# untitled.net
KiCad netlist of a schematic drawn in EAGLE
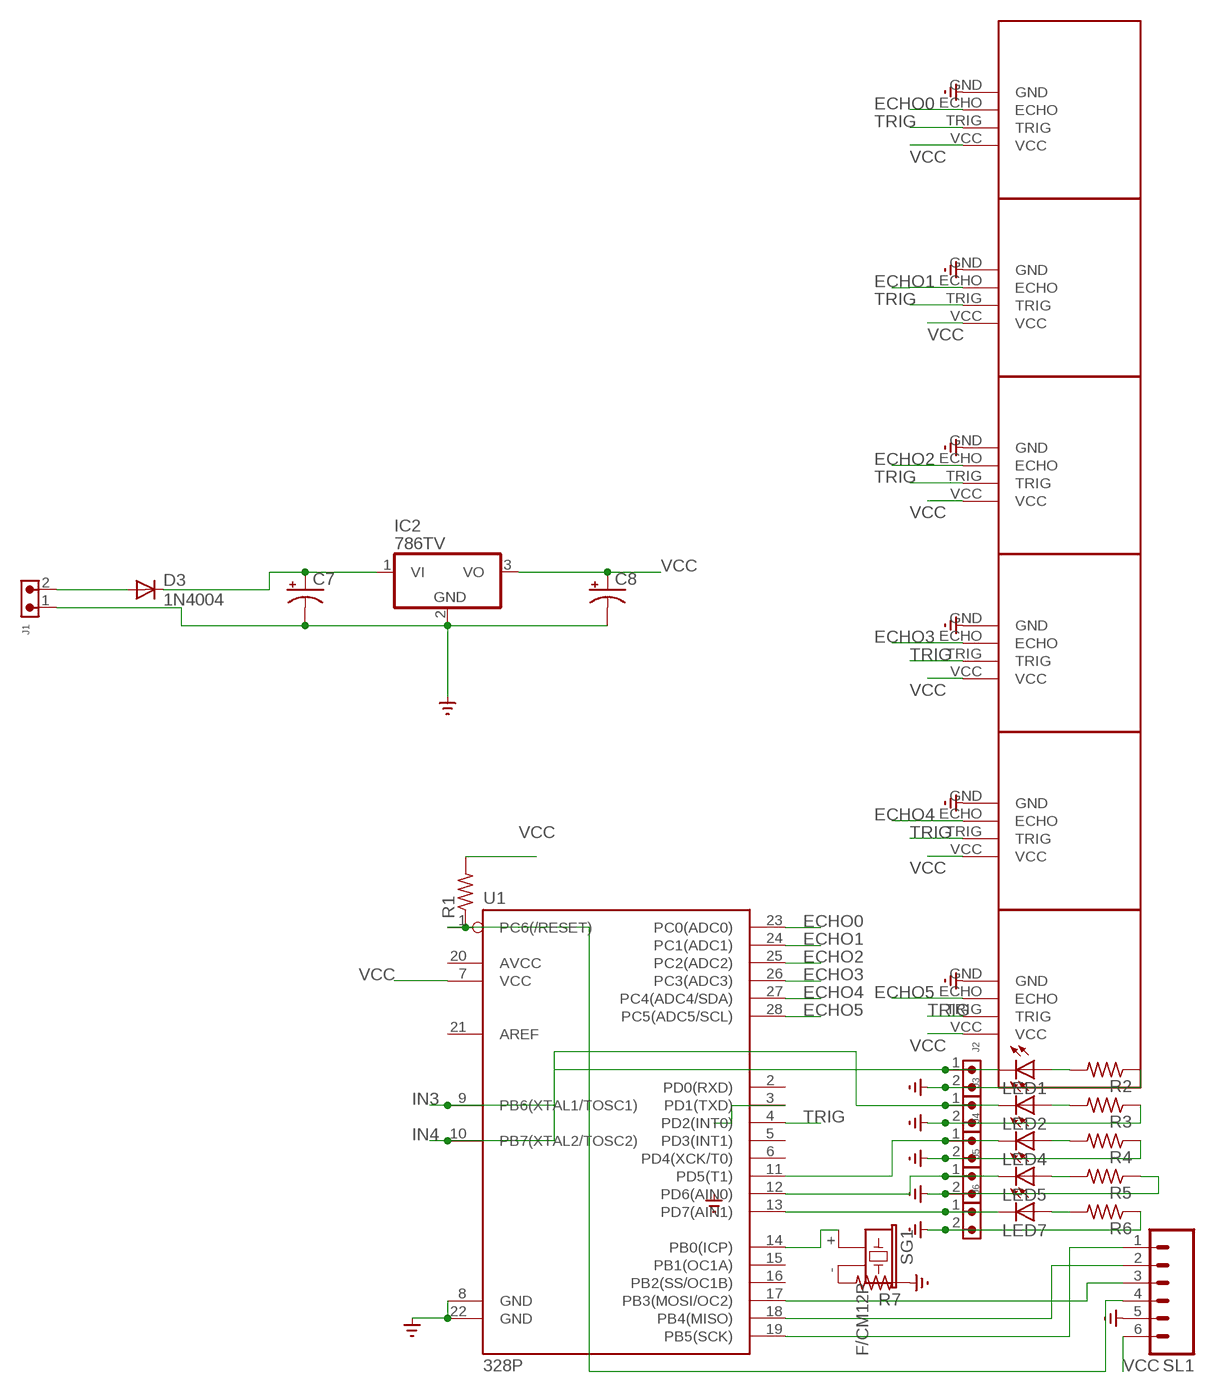
[diagram p0: schematic, sheet 1]

(export (version "E")
  (design (tool "Eeschema 10.0.6"))
  (components
    (comp (ref "C7")
      (value "CAPACITOR-PE5-10.5")
      (footprint "eagle-import:E5-10,5")
      (libsource (lib "eagle-import") (part "CAPACITOR-PE5-10.5"))
    )
    (comp (ref "C8")
      (value "CAPACITOR-PE5-6")
      (footprint "eagle-import:E5-6")
      (libsource (lib "eagle-import") (part "CAPACITOR-PE5-6"))
    )
    (comp (ref "D3")
      (value "1N4004")
      (footprint "eagle-import:DO41-10")
      (libsource (lib "eagle-import") (part "1N4004"))
    )
    (comp (ref "IC2")
      (value "786TV")
      (footprint "eagle-import:TO220V")
      (libsource (lib "eagle-import") (part "78TV6"))
    )
    (comp (ref "J1")
      (value "691305530002")
      (footprint "eagle-import:691305530002")
      (libsource (lib "eagle-import") (part "691305530002"))
    )
    (comp (ref "J2")
      (value "691305530002")
      (footprint "eagle-import:691305530002")
      (libsource (lib "eagle-import") (part "691305530002"))
    )
    (comp (ref "J3")
      (value "691305530002")
      (footprint "eagle-import:691305530002")
      (libsource (lib "eagle-import") (part "691305530002"))
    )
    (comp (ref "J4")
      (value "691305530002")
      (footprint "eagle-import:691305530002")
      (libsource (lib "eagle-import") (part "691305530002"))
    )
    (comp (ref "J5")
      (value "691305530002")
      (footprint "eagle-import:691305530002")
      (libsource (lib "eagle-import") (part "691305530002"))
    )
    (comp (ref "J6")
      (value "691305530002")
      (footprint "eagle-import:691305530002")
      (libsource (lib "eagle-import") (part "691305530002"))
    )
    (comp (ref "LED1")
      (value "LED5MM")
      (footprint "eagle-import:LED5MM")
      (libsource (lib "eagle-import") (part "LED5MM"))
    )
    (comp (ref "LED2")
      (value "LED5MM")
      (footprint "eagle-import:LED5MM")
      (libsource (lib "eagle-import") (part "LED5MM"))
    )
    (comp (ref "LED4")
      (value "LED5MM")
      (footprint "eagle-import:LED5MM")
      (libsource (lib "eagle-import") (part "LED5MM"))
    )
    (comp (ref "LED5")
      (value "LED5MM")
      (footprint "eagle-import:LED5MM")
      (libsource (lib "eagle-import") (part "LED5MM"))
    )
    (comp (ref "LED7")
      (value "LED5MM")
      (footprint "eagle-import:LED5MM")
      (libsource (lib "eagle-import") (part "LED5MM"))
    )
    (comp (ref "R1")
      (value "R-US_0207/9")
      (footprint "eagle-import:0207_9")
      (libsource (lib "eagle-import") (part "R-US_0207/9"))
    )
    (comp (ref "R2")
      (value "R-US_0207/9")
      (footprint "eagle-import:0207_9")
      (libsource (lib "eagle-import") (part "R-US_0207/9"))
    )
    (comp (ref "R3")
      (value "R-US_0207/9")
      (footprint "eagle-import:0207_9")
      (libsource (lib "eagle-import") (part "R-US_0207/9"))
    )
    (comp (ref "R4")
      (value "R-US_0207/9")
      (footprint "eagle-import:0207_9")
      (libsource (lib "eagle-import") (part "R-US_0207/9"))
    )
    (comp (ref "R5")
      (value "R-US_0207/9")
      (footprint "eagle-import:0207_9")
      (libsource (lib "eagle-import") (part "R-US_0207/9"))
    )
    (comp (ref "R6")
      (value "R-US_0207/9")
      (footprint "eagle-import:0207_9")
      (libsource (lib "eagle-import") (part "R-US_0207/9"))
    )
    (comp (ref "R7")
      (value "R-US_0207/9")
      (footprint "eagle-import:0207_9")
      (libsource (lib "eagle-import") (part "R-US_0207/9"))
    )
    (comp (ref "SG1")
      (value "F/CM12P")
      (footprint "eagle-import:F_CM12P")
      (libsource (lib "eagle-import") (part "F/CM12P"))
    )
    (comp (ref "SL1")
      (value "M06")
      (footprint "eagle-import:06P")
      (libsource (lib "eagle-import") (part "M06"))
    )
    (comp (ref "U$1")
      (value "SRO4M")
      (footprint "eagle-import:SRO4M")
      (libsource (lib "eagle-import") (part "SRO4M"))
    )
    (comp (ref "U$2")
      (value "SRO4M")
      (footprint "eagle-import:SRO4M")
      (libsource (lib "eagle-import") (part "SRO4M"))
    )
    (comp (ref "U$3")
      (value "SRO4M")
      (footprint "eagle-import:SRO4M")
      (libsource (lib "eagle-import") (part "SRO4M"))
    )
    (comp (ref "U$4")
      (value "SRO4M")
      (footprint "eagle-import:SRO4M")
      (libsource (lib "eagle-import") (part "SRO4M"))
    )
    (comp (ref "U$5")
      (value "SRO4M")
      (footprint "eagle-import:SRO4M")
      (libsource (lib "eagle-import") (part "SRO4M"))
    )
    (comp (ref "U$6")
      (value "SRO4M")
      (footprint "eagle-import:SRO4M")
      (libsource (lib "eagle-import") (part "SRO4M"))
    )
    (comp (ref "U1")
      (value "328P")
      (footprint "eagle-import:DIP28")
      (libsource (lib "eagle-import") (part "ATMEGA328P_PDIP"))
    )
  )
  (nets
    (net (code "1") (name "/ECHO0") (class "Default")
      (node (ref "U$6") (pin "ECHO") (pinfunction "ECHO_ECHO") (pintype "bidirectional"))
      (node (ref "U1") (pin "23") (pinfunction "PC0(ADC0)_23") (pintype "bidirectional"))
    )
    (net (code "2") (name "/ECHO1") (class "Default")
      (node (ref "U$1") (pin "ECHO") (pinfunction "ECHO_ECHO") (pintype "bidirectional"))
      (node (ref "U1") (pin "24") (pinfunction "PC1(ADC1)_24") (pintype "bidirectional"))
    )
    (net (code "3") (name "/ECHO2") (class "Default")
      (node (ref "U$2") (pin "ECHO") (pinfunction "ECHO_ECHO") (pintype "bidirectional"))
      (node (ref "U1") (pin "25") (pinfunction "PC2(ADC2)_25") (pintype "bidirectional"))
    )
    (net (code "4") (name "/ECHO3") (class "Default")
      (node (ref "U$4") (pin "ECHO") (pinfunction "ECHO_ECHO") (pintype "bidirectional"))
      (node (ref "U1") (pin "26") (pinfunction "PC3(ADC3)_26") (pintype "bidirectional"))
    )
    (net (code "5") (name "/ECHO4") (class "Default")
      (node (ref "U$3") (pin "ECHO") (pinfunction "ECHO_ECHO") (pintype "bidirectional"))
      (node (ref "U1") (pin "27") (pinfunction "PC4(ADC4/SDA)_27") (pintype "bidirectional"))
    )
    (net (code "6") (name "/ECHO5") (class "Default")
      (node (ref "U$5") (pin "ECHO") (pinfunction "ECHO_ECHO") (pintype "bidirectional"))
      (node (ref "U1") (pin "28") (pinfunction "PC5(ADC5/SCL)_28") (pintype "bidirectional"))
    )
    (net (code "7") (name "/IN3") (class "Default")
      (node (ref "J2") (pin "1") (pinfunction "1_1") (pintype "passive"))
      (node (ref "LED1") (pin "K") (pinfunction "C_K") (pintype "passive"))
      (node (ref "U1") (pin "9") (pinfunction "PB6(XTAL1/TOSC1)_9") (pintype "bidirectional"))
    )
    (net (code "8") (name "/IN4") (class "Default")
      (node (ref "J3") (pin "1") (pinfunction "1_1") (pintype "passive"))
      (node (ref "LED2") (pin "K") (pinfunction "C_K") (pintype "passive"))
      (node (ref "U1") (pin "10") (pinfunction "PB7(XTAL2/TOSC2)_10") (pintype "bidirectional"))
    )
    (net (code "9") (name "/TRIG") (class "Default")
      (node (ref "U$1") (pin "TRIG") (pinfunction "TRIG_TRIG") (pintype "bidirectional"))
      (node (ref "U$2") (pin "TRIG") (pinfunction "TRIG_TRIG") (pintype "bidirectional"))
      (node (ref "U$3") (pin "TRIG") (pinfunction "TRIG_TRIG") (pintype "bidirectional"))
      (node (ref "U$4") (pin "TRIG") (pinfunction "TRIG_TRIG") (pintype "bidirectional"))
      (node (ref "U$5") (pin "TRIG") (pinfunction "TRIG_TRIG") (pintype "bidirectional"))
      (node (ref "U$6") (pin "TRIG") (pinfunction "TRIG_TRIG") (pintype "bidirectional"))
      (node (ref "U1") (pin "4") (pinfunction "PD2(INT0)_4") (pintype "bidirectional"))
    )
    (net (code "10") (name "/VCC") (class "Default")
      (node (ref "C8") (pin "+") (pinfunction "+_+") (pintype "passive"))
      (node (ref "IC2") (pin "3") (pinfunction "VO_3") (pintype "passive"))
      (node (ref "R1") (pin "2") (pinfunction "2_2") (pintype "passive"))
      (node (ref "SL1") (pin "6") (pinfunction "6_6") (pintype "passive"))
      (node (ref "U$1") (pin "VCC") (pinfunction "VCC_VCC") (pintype "bidirectional"))
      (node (ref "U$2") (pin "VCC") (pinfunction "VCC_VCC") (pintype "bidirectional"))
      (node (ref "U$3") (pin "VCC") (pinfunction "VCC_VCC") (pintype "bidirectional"))
      (node (ref "U$4") (pin "VCC") (pinfunction "VCC_VCC") (pintype "bidirectional"))
      (node (ref "U$5") (pin "VCC") (pinfunction "VCC_VCC") (pintype "bidirectional"))
      (node (ref "U$6") (pin "VCC") (pinfunction "VCC_VCC") (pintype "bidirectional"))
      (node (ref "U1") (pin "7") (pinfunction "VCC_7") (pintype "bidirectional"))
    )
    (net (code "11") (name "Net-(D3-PadA)") (class "Default")
      (node (ref "D3") (pin "A") (pinfunction "A_A") (pintype "passive"))
      (node (ref "J1") (pin "2") (pinfunction "2_2") (pintype "passive"))
    )
    (net (code "12") (name "Net-(IC2-VI)") (class "Default")
      (node (ref "C7") (pin "+") (pinfunction "+_+") (pintype "passive"))
      (node (ref "D3") (pin "C") (pinfunction "C_C") (pintype "passive"))
      (node (ref "IC2") (pin "1") (pinfunction "VI_1") (pintype "input"))
    )
    (net (code "13") (name "Net-(LED1-PadA)") (class "Default")
      (node (ref "LED1") (pin "A") (pinfunction "A_A") (pintype "passive"))
      (node (ref "R2") (pin "2") (pinfunction "2_2") (pintype "passive"))
    )
    (net (code "14") (name "Net-(LED2-PadA)") (class "Default")
      (node (ref "LED2") (pin "A") (pinfunction "A_A") (pintype "passive"))
      (node (ref "R3") (pin "2") (pinfunction "2_2") (pintype "passive"))
    )
    (net (code "15") (name "Net-(LED4-C)") (class "Default")
      (node (ref "J4") (pin "1") (pinfunction "1_1") (pintype "passive"))
      (node (ref "LED4") (pin "K") (pinfunction "C_K") (pintype "passive"))
      (node (ref "U1") (pin "11") (pinfunction "PD5(T1)_11") (pintype "bidirectional"))
    )
    (net (code "16") (name "Net-(LED4-PadA)") (class "Default")
      (node (ref "LED4") (pin "A") (pinfunction "A_A") (pintype "passive"))
      (node (ref "R4") (pin "2") (pinfunction "2_2") (pintype "passive"))
    )
    (net (code "17") (name "Net-(LED5-C)") (class "Default")
      (node (ref "J5") (pin "1") (pinfunction "1_1") (pintype "passive"))
      (node (ref "LED5") (pin "K") (pinfunction "C_K") (pintype "passive"))
      (node (ref "U1") (pin "12") (pinfunction "PD6(AIN0)_12") (pintype "bidirectional"))
    )
    (net (code "18") (name "Net-(LED5-PadA)") (class "Default")
      (node (ref "LED5") (pin "A") (pinfunction "A_A") (pintype "passive"))
      (node (ref "R5") (pin "2") (pinfunction "2_2") (pintype "passive"))
    )
    (net (code "19") (name "Net-(LED7-C)") (class "Default")
      (node (ref "J6") (pin "1") (pinfunction "1_1") (pintype "passive"))
      (node (ref "LED7") (pin "K") (pinfunction "C_K") (pintype "passive"))
      (node (ref "U1") (pin "13") (pinfunction "PD7(AIN1)_13") (pintype "bidirectional"))
    )
    (net (code "20") (name "Net-(LED7-PadA)") (class "Default")
      (node (ref "LED7") (pin "A") (pinfunction "A_A") (pintype "passive"))
      (node (ref "R6") (pin "2") (pinfunction "2_2") (pintype "passive"))
    )
    (net (code "21") (name "Net-(SG1-1)") (class "Default")
      (node (ref "SG1") (pin "+") (pinfunction "1_+") (pintype "passive"))
      (node (ref "U1") (pin "14") (pinfunction "PB0(ICP)_14") (pintype "bidirectional"))
    )
    (net (code "22") (name "Net-(SG1-2)") (class "Default")
      (node (ref "R7") (pin "2") (pinfunction "2_2") (pintype "passive"))
      (node (ref "SG1") (pin "-") (pinfunction "2_-") (pintype "passive"))
    )
    (net (code "23") (name "Net-(U1-PB3(MOSI{slash}OC2))") (class "Default")
      (node (ref "SL1") (pin "3") (pinfunction "3_3") (pintype "passive"))
      (node (ref "U1") (pin "17") (pinfunction "PB3(MOSI/OC2)_17") (pintype "bidirectional"))
    )
    (net (code "24") (name "Net-(U1-PB4(MISO))") (class "Default")
      (node (ref "SL1") (pin "2") (pinfunction "2_2") (pintype "passive"))
      (node (ref "U1") (pin "18") (pinfunction "PB4(MISO)_18") (pintype "bidirectional"))
    )
    (net (code "25") (name "Net-(U1-PB5(SCK))") (class "Default")
      (node (ref "SL1") (pin "1") (pinfunction "1_1") (pintype "passive"))
      (node (ref "U1") (pin "19") (pinfunction "PB5(SCK)_19") (pintype "bidirectional"))
    )
    (net (code "26") (name "Net-(U1-PC6({slash}RESET))") (class "Default")
      (node (ref "R1") (pin "1") (pinfunction "1_1") (pintype "passive"))
      (node (ref "SL1") (pin "4") (pinfunction "4_4") (pintype "passive"))
      (node (ref "U1") (pin "1") (pinfunction "PC6(/RESET)_1") (pintype "bidirectional"))
    )
    (net (code "27") (name "SUPPLY_BRASTAN_GND_") (class "Default")
      (node (ref "C7") (pin "-") (pinfunction "-_-") (pintype "passive"))
      (node (ref "C8") (pin "-") (pinfunction "-_-") (pintype "passive"))
      (node (ref "IC2") (pin "2") (pinfunction "GND_2") (pintype "passive"))
      (node (ref "J1") (pin "1") (pinfunction "1_1") (pintype "passive"))
      (node (ref "J2") (pin "2") (pinfunction "2_2") (pintype "passive"))
      (node (ref "J3") (pin "2") (pinfunction "2_2") (pintype "passive"))
      (node (ref "J4") (pin "2") (pinfunction "2_2") (pintype "passive"))
      (node (ref "J5") (pin "2") (pinfunction "2_2") (pintype "passive"))
      (node (ref "J6") (pin "2") (pinfunction "2_2") (pintype "passive"))
      (node (ref "R2") (pin "1") (pinfunction "1_1") (pintype "passive"))
      (node (ref "R3") (pin "1") (pinfunction "1_1") (pintype "passive"))
      (node (ref "R4") (pin "1") (pinfunction "1_1") (pintype "passive"))
      (node (ref "R5") (pin "1") (pinfunction "1_1") (pintype "passive"))
      (node (ref "R6") (pin "1") (pinfunction "1_1") (pintype "passive"))
      (node (ref "R7") (pin "1") (pinfunction "1_1") (pintype "passive"))
      (node (ref "SL1") (pin "5") (pinfunction "5_5") (pintype "passive"))
      (node (ref "U$1") (pin "GND") (pinfunction "GND_GND") (pintype "bidirectional"))
      (node (ref "U$2") (pin "GND") (pinfunction "GND_GND") (pintype "bidirectional"))
      (node (ref "U$3") (pin "GND") (pinfunction "GND_GND") (pintype "bidirectional"))
      (node (ref "U$4") (pin "GND") (pinfunction "GND_GND") (pintype "bidirectional"))
      (node (ref "U$5") (pin "GND") (pinfunction "GND_GND") (pintype "bidirectional"))
      (node (ref "U$6") (pin "GND") (pinfunction "GND_GND") (pintype "bidirectional"))
      (node (ref "U1") (pin "22") (pinfunction "GND_22") (pintype "bidirectional"))
      (node (ref "U1") (pin "8") (pinfunction "GND_8") (pintype "bidirectional"))
    )
    (net (code "28") (name "unconnected-(U1-AREF-Pad21)") (class "Default")
      (node (ref "U1") (pin "21") (pinfunction "AREF_21") (pintype "bidirectional"))
    )
    (net (code "29") (name "unconnected-(U1-AVCC-Pad20)") (class "Default")
      (node (ref "U1") (pin "20") (pinfunction "AVCC_20") (pintype "bidirectional"))
    )
    (net (code "30") (name "unconnected-(U1-PB1(OC1A)-Pad15)") (class "Default")
      (node (ref "U1") (pin "15") (pinfunction "PB1(OC1A)_15") (pintype "bidirectional"))
    )
    (net (code "31") (name "unconnected-(U1-PB2(SS{slash}OC1B)-Pad16)") (class "Default")
      (node (ref "U1") (pin "16") (pinfunction "PB2(SS/OC1B)_16") (pintype "bidirectional"))
    )
    (net (code "32") (name "unconnected-(U1-PD0(RXD)-Pad2)") (class "Default")
      (node (ref "U1") (pin "2") (pinfunction "PD0(RXD)_2") (pintype "bidirectional"))
    )
    (net (code "33") (name "unconnected-(U1-PD1(TXD)-Pad3)") (class "Default")
      (node (ref "U1") (pin "3") (pinfunction "PD1(TXD)_3") (pintype "bidirectional"))
    )
    (net (code "34") (name "unconnected-(U1-PD3(INT1)-Pad5)") (class "Default")
      (node (ref "U1") (pin "5") (pinfunction "PD3(INT1)_5") (pintype "bidirectional"))
    )
    (net (code "35") (name "unconnected-(U1-PD4(XCK{slash}T0)-Pad6)") (class "Default")
      (node (ref "U1") (pin "6") (pinfunction "PD4(XCK/T0)_6") (pintype "bidirectional"))
    )
  )
)
